# 04_FEATHER-CONNECTION.net
KiCad netlist of a schematic drawn in Altium Designer
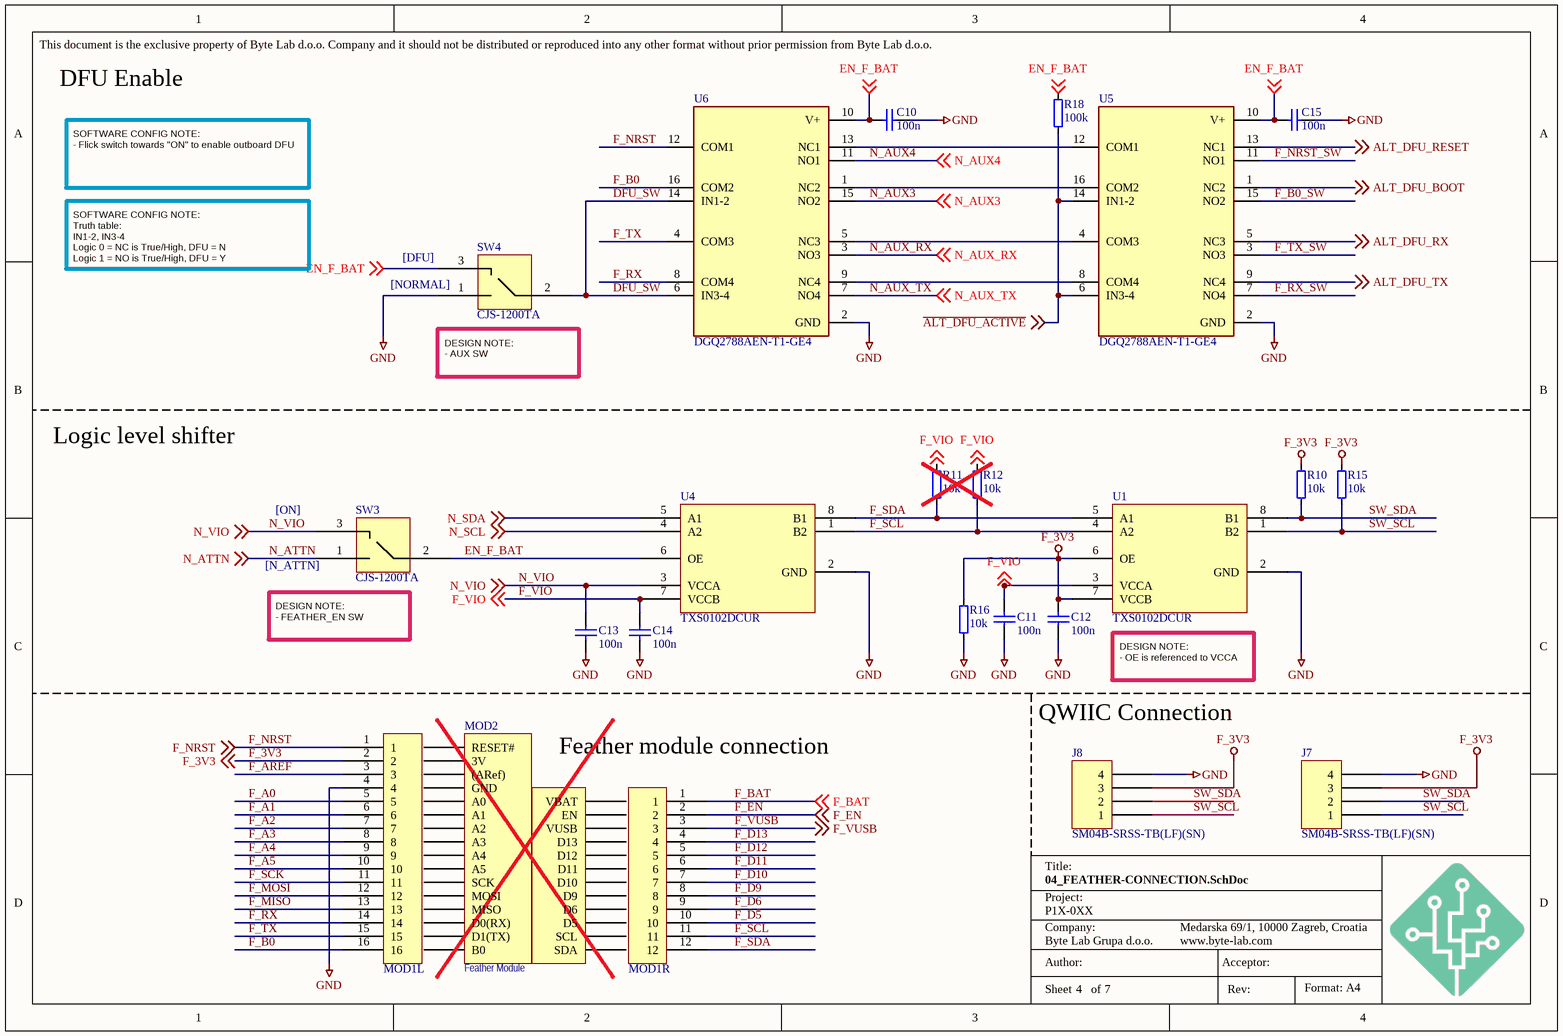
[diagram p0: 04_FEATHER-CONNECTION.SchDoc]

(export (version "E")
  (design (tool "Eeschema 10.0.6"))
  (components
    (comp (ref "C10")
      (value "100n")
      (footprint "C-0402")
      (description "Capacitor ceramic 100n ±10% X7R 16V 0402")
      (fields
        (field (name "BL PART NUMBER") "2000-908")
        (field (name "DRAWN_BY") "Puskar")
        (field (name "CHECKED_BY") "Dodig")
      )
      (libsource (lib "BL_Passive") (part "C0402-100n-16V-X7R"))
    )
    (comp (ref "C11")
      (value "100n")
      (footprint "C-0402")
      (description "Capacitor ceramic 100n ±10% X7R 16V 0402")
      (fields
        (field (name "BL PART NUMBER") "2000-908")
        (field (name "DRAWN_BY") "Puskar")
        (field (name "CHECKED_BY") "Dodig")
      )
      (libsource (lib "BL_Passive") (part "C0402-100n-16V-X7R"))
    )
    (comp (ref "C12")
      (value "100n")
      (footprint "C-0402")
      (description "Capacitor ceramic 100n ±10% X7R 16V 0402")
      (fields
        (field (name "BL PART NUMBER") "2000-908")
        (field (name "DRAWN_BY") "Puskar")
        (field (name "CHECKED_BY") "Dodig")
      )
      (libsource (lib "BL_Passive") (part "C0402-100n-16V-X7R"))
    )
    (comp (ref "C13")
      (value "100n")
      (footprint "C-0402")
      (description "Capacitor ceramic 100n ±10% X7R 16V 0402")
      (fields
        (field (name "BL PART NUMBER") "2000-908")
        (field (name "DRAWN_BY") "Puskar")
        (field (name "CHECKED_BY") "Dodig")
      )
      (libsource (lib "BL_Passive") (part "C0402-100n-16V-X7R"))
    )
    (comp (ref "C14")
      (value "100n")
      (footprint "C-0402")
      (description "Capacitor ceramic 100n ±10% X7R 16V 0402")
      (fields
        (field (name "BL PART NUMBER") "2000-908")
        (field (name "DRAWN_BY") "Puskar")
        (field (name "CHECKED_BY") "Dodig")
      )
      (libsource (lib "BL_Passive") (part "C0402-100n-16V-X7R"))
    )
    (comp (ref "C15")
      (value "100n")
      (footprint "C-0402")
      (description "Capacitor ceramic 100n ±10% X7R 16V 0402")
      (fields
        (field (name "BL PART NUMBER") "2000-908")
        (field (name "DRAWN_BY") "Puskar")
        (field (name "CHECKED_BY") "Dodig")
      )
      (libsource (lib "BL_Passive") (part "C0402-100n-16V-X7R"))
    )
    (comp (ref "J7")
      (value "SM04B-SRSS-TB(LF)(SN)")
      (footprint "JST SM04B-SRSS-TB")
      (description "CONN HEADER SH 4POS SIDE 1MM TIN")
      (fields
        (field (name "MANUFACTURER") "JST Sales America Inc.")
        (field (name "BL PART NUMBER") "2002-058")
        (field (name "DRAWN_BY") "Blues Wireless")
      )
      (libsource (lib "n21-p2") (part "SM04B-SRSS-TB(LF)(SN)"))
    )
    (comp (ref "J8")
      (value "SM04B-SRSS-TB(LF)(SN)")
      (footprint "JST SM04B-SRSS-TB")
      (description "CONN HEADER SH 4POS SIDE 1MM TIN")
      (fields
        (field (name "MANUFACTURER") "JST Sales America Inc.")
        (field (name "BL PART NUMBER") "2002-058")
        (field (name "DRAWN_BY") "Blues Wireless")
      )
      (libsource (lib "n21-p2") (part "SM04B-SRSS-TB(LF)(SN)"))
    )
    (comp (ref "MOD1L")
      (value "CES-116-01-L-S")
      (footprint "16PIN_254MM")
      (description "Socket 16-Pin, 0.100 in")
      (fields
        (field (name "MANUFACTURER") "Samtec Inc.")
        (field (name "BL PART NUMBER") "2007-463")
        (field (name "DRAWN_BY") "Blues Wireless")
      )
      (libsource (lib "n21-p2") (part "SOCKET_LFB_16"))
    )
    (comp (ref "MOD1R")
      (value "CES-112-01-L-S")
      (footprint "12PIN_254MM")
      (description "Socket 12-Pin, 0.100 in")
      (fields
        (field (name "MANUFACTURER") "Samtec Inc.")
        (field (name "BL PART NUMBER") "2007-464")
        (field (name "DRAWN_BY") "Blues Wireless")
      )
      (libsource (lib "n21-p2") (part "SOCKET_LFB_12"))
    )
    (comp (ref "MOD2")
      (value "Feather Module")
      (footprint "BLUES_WIRELESS_SWAN_2-54_HEADERS")
      (description "Typical Adafruit Feather Pinout")
      (libsource (lib "n21-p2") (part "ADAFRUIT_FEATHER_COMMON_1"))
    )
    (comp (ref "R10")
      (value "10k")
      (footprint "R-0402")
      (description "Resistor 10k ±1% 0402")
      (fields
        (field (name "BL PART NUMBER") "2000-729")
        (field (name "CHECKED_BY") "Dodig")
        (field (name "DRAWN_BY") "Puskar")
      )
      (libsource (lib "BL_Passive") (part "R0402-10k-1"))
    )
    (comp (ref "R11")
      (value "10k")
      (footprint "R-0402")
      (description "Resistor 10k ±1% 0402")
      (fields
        (field (name "BL PART NUMBER") "2000-729")
        (field (name "CHECKED_BY") "Dodig")
        (field (name "DRAWN_BY") "Puskar")
      )
      (libsource (lib "BL_Passive") (part "R0402-10k-1"))
    )
    (comp (ref "R12")
      (value "10k")
      (footprint "R-0402")
      (description "Resistor 10k ±1% 0402")
      (fields
        (field (name "BL PART NUMBER") "2000-729")
        (field (name "CHECKED_BY") "Dodig")
        (field (name "DRAWN_BY") "Puskar")
      )
      (libsource (lib "BL_Passive") (part "R0402-10k-1"))
    )
    (comp (ref "R15")
      (value "10k")
      (footprint "R-0402")
      (description "Resistor 10k ±1% 0402")
      (fields
        (field (name "BL PART NUMBER") "2000-729")
        (field (name "CHECKED_BY") "Dodig")
        (field (name "DRAWN_BY") "Puskar")
      )
      (libsource (lib "BL_Passive") (part "R0402-10k-1"))
    )
    (comp (ref "R16")
      (value "10k")
      (footprint "R-0402")
      (description "Resistor 10k ±1% 0402")
      (fields
        (field (name "BL PART NUMBER") "2000-729")
        (field (name "CHECKED_BY") "Dodig")
        (field (name "DRAWN_BY") "Puskar")
      )
      (libsource (lib "BL_Passive") (part "R0402-10k-1"))
    )
    (comp (ref "R18")
      (value "100k")
      (footprint "R-0402")
      (description "Resistor 100k ±1% 0402")
      (fields
        (field (name "BL PART NUMBER") "2000-727")
        (field (name "CHECKED_BY") "Dodig")
        (field (name "DRAWN_BY") "Puskar")
      )
      (libsource (lib "BL_Passive") (part "R0402-100k-1"))
    )
    (comp (ref "SW3")
      (value "CJS-1200TA")
      (footprint "SW_CJS-1200TA")
      (description "Switch Slide N.O./N.C. SPDT Raised Slide 0.1A 24VDC J-Hook SMD Embossed T/R")
      (fields
        (field (name "MANUFACTURER") "Nidec Copal")
        (field (name "BL PART NUMBER") "2007-456")
        (field (name "DRAWN_BY") "Blues Wireless")
      )
      (libsource (lib "n21-p2") (part "CJS-1200TA"))
    )
    (comp (ref "SW4")
      (value "CJS-1200TA")
      (footprint "SW_CJS-1200TA")
      (description "Switch Slide N.O./N.C. SPDT Raised Slide 0.1A 24VDC J-Hook SMD Embossed T/R")
      (fields
        (field (name "MANUFACTURER") "Nidec Copal")
        (field (name "BL PART NUMBER") "2007-456")
        (field (name "DRAWN_BY") "Blues Wireless")
      )
      (libsource (lib "n21-p2") (part "CJS-1200TA"))
    )
    (comp (ref "U1")
      (value "TXS0102DCUR")
      (footprint "SOP50P310X90-8N")
      (fields
        (field (name "MANUFACTURER") "Texas Instruments")
        (field (name "BL PART NUMBER") "2007-455")
        (field (name "DRAWN_BY") "Blues Wireless")
      )
      (libsource (lib "n21-p2") (part "TXS0102DCUR"))
    )
    (comp (ref "U4")
      (value "TXS0102DCUR")
      (footprint "SOP50P310X90-8N")
      (fields
        (field (name "MANUFACTURER") "Texas Instruments")
        (field (name "BL PART NUMBER") "2007-455")
        (field (name "DRAWN_BY") "Blues Wireless")
      )
      (libsource (lib "n21-p2") (part "TXS0102DCUR"))
    )
    (comp (ref "U5")
      (value "DGQ2788AEN-T1-GE4")
      (footprint "QFN40P260X180X60-16N")
      (description "Analog Switch Quad SPDT Automotive 16-Pin Mini-QFN T/R")
      (fields
        (field (name "MANUFACTURER") "Vishay")
        (field (name "BL PART NUMBER") "2007-457")
        (field (name "DRAWN_BY") "Blues Wireless")
      )
      (libsource (lib "n21-p2") (part "DGQ2788AEN-T1-GE4"))
    )
    (comp (ref "U6")
      (value "DGQ2788AEN-T1-GE4")
      (footprint "QFN40P260X180X60-16N")
      (description "Analog Switch Quad SPDT Automotive 16-Pin Mini-QFN T/R")
      (fields
        (field (name "MANUFACTURER") "Vishay")
        (field (name "BL PART NUMBER") "2007-457")
        (field (name "DRAWN_BY") "Blues Wireless")
      )
      (libsource (lib "n21-p2") (part "DGQ2788AEN-T1-GE4"))
    )
  )
  (nets
    (net (code "1") (name "/DFU_SW") (class "Default")
      (node (ref "SW4") (pin "2") (pinfunction "2_2") (pintype "passive"))
      (node (ref "U6") (pin "14") (pinfunction "IN1-2_14") (pintype "passive"))
      (node (ref "U6") (pin "6") (pinfunction "IN3-4_6") (pintype "passive"))
    )
    (net (code "2") (name "/F_A0") (class "Default")
      (node (ref "MOD1L") (pin "5") (pinfunction "5_5") (pintype "passive"))
    )
    (net (code "3") (name "/F_A1") (class "Default")
      (node (ref "MOD1L") (pin "6") (pinfunction "6_6") (pintype "passive"))
    )
    (net (code "4") (name "/F_A2") (class "Default")
      (node (ref "MOD1L") (pin "7") (pinfunction "7_7") (pintype "passive"))
    )
    (net (code "5") (name "/F_A3") (class "Default")
      (node (ref "MOD1L") (pin "8") (pinfunction "8_8") (pintype "passive"))
    )
    (net (code "6") (name "/F_A4") (class "Default")
      (node (ref "MOD1L") (pin "9") (pinfunction "9_9") (pintype "passive"))
    )
    (net (code "7") (name "/F_A5") (class "Default")
      (node (ref "MOD1L") (pin "10") (pinfunction "10_10") (pintype "passive"))
    )
    (net (code "8") (name "/F_AREF") (class "Default")
      (node (ref "MOD1L") (pin "3") (pinfunction "3_3") (pintype "passive"))
    )
    (net (code "9") (name "/F_B0") (class "Default")
      (node (ref "MOD1L") (pin "16") (pinfunction "16_16") (pintype "passive"))
      (node (ref "U6") (pin "16") (pinfunction "COM2_16") (pintype "passive"))
    )
    (net (code "10") (name "/F_B0_SW") (class "Default")
      (node (ref "U5") (pin "15") (pinfunction "NO2_15") (pintype "passive"))
    )
    (net (code "11") (name "/F_D5") (class "Default")
      (node (ref "MOD1R") (pin "10") (pinfunction "10_10") (pintype "passive"))
    )
    (net (code "12") (name "/F_D6") (class "Default")
      (node (ref "MOD1R") (pin "9") (pinfunction "9_9") (pintype "passive"))
    )
    (net (code "13") (name "/F_D9") (class "Default")
      (node (ref "MOD1R") (pin "8") (pinfunction "8_8") (pintype "passive"))
    )
    (net (code "14") (name "/F_D10") (class "Default")
      (node (ref "MOD1R") (pin "7") (pinfunction "7_7") (pintype "passive"))
    )
    (net (code "15") (name "/F_D11") (class "Default")
      (node (ref "MOD1R") (pin "6") (pinfunction "6_6") (pintype "passive"))
    )
    (net (code "16") (name "/F_D12") (class "Default")
      (node (ref "MOD1R") (pin "5") (pinfunction "5_5") (pintype "passive"))
    )
    (net (code "17") (name "/F_D13") (class "Default")
      (node (ref "MOD1R") (pin "4") (pinfunction "4_4") (pintype "passive"))
    )
    (net (code "18") (name "/F_MISO") (class "Default")
      (node (ref "MOD1L") (pin "13") (pinfunction "13_13") (pintype "passive"))
    )
    (net (code "19") (name "/F_MOSI") (class "Default")
      (node (ref "MOD1L") (pin "12") (pinfunction "12_12") (pintype "passive"))
    )
    (net (code "20") (name "/F_NRST_SW") (class "Default")
      (node (ref "U5") (pin "11") (pinfunction "NO1_11") (pintype "passive"))
    )
    (net (code "21") (name "/F_RX") (class "Default")
      (node (ref "MOD1L") (pin "14") (pinfunction "14_14") (pintype "passive"))
      (node (ref "U6") (pin "8") (pinfunction "COM4_8") (pintype "passive"))
    )
    (net (code "22") (name "/F_RX_SW") (class "Default")
      (node (ref "U5") (pin "7") (pinfunction "NO4_7") (pintype "passive"))
    )
    (net (code "23") (name "/F_SCK") (class "Default")
      (node (ref "MOD1L") (pin "11") (pinfunction "11_11") (pintype "passive"))
    )
    (net (code "24") (name "/F_SCL") (class "Default")
      (node (ref "MOD1R") (pin "11") (pinfunction "11_11") (pintype "passive"))
      (node (ref "R12") (pin "1") (pintype "passive"))
      (node (ref "U1") (pin "4") (pinfunction "A2_4") (pintype "passive"))
      (node (ref "U4") (pin "1") (pinfunction "B2_1") (pintype "passive"))
    )
    (net (code "25") (name "/F_SDA") (class "Default")
      (node (ref "MOD1R") (pin "12") (pinfunction "12_12") (pintype "passive"))
      (node (ref "R11") (pin "1") (pintype "passive"))
      (node (ref "U1") (pin "5") (pinfunction "A1_5") (pintype "passive"))
      (node (ref "U4") (pin "8") (pinfunction "B1_8") (pintype "passive"))
    )
    (net (code "26") (name "/F_TX") (class "Default")
      (node (ref "MOD1L") (pin "15") (pinfunction "15_15") (pintype "passive"))
      (node (ref "U6") (pin "4") (pinfunction "COM3_4") (pintype "passive"))
    )
    (net (code "27") (name "/F_TX_SW") (class "Default")
      (node (ref "U5") (pin "3") (pinfunction "NO3_3") (pintype "passive"))
    )
    (net (code "28") (name "/SW_SCL") (class "Default")
      (node (ref "J7") (pin "1") (pinfunction "1_1") (pintype "passive"))
      (node (ref "J8") (pin "1") (pinfunction "1_1") (pintype "passive"))
      (node (ref "R15") (pin "1") (pintype "passive"))
      (node (ref "U1") (pin "1") (pinfunction "B2_1") (pintype "passive"))
    )
    (net (code "29") (name "/SW_SDA") (class "Default")
      (node (ref "J7") (pin "2") (pinfunction "2_2") (pintype "passive"))
      (node (ref "J8") (pin "2") (pinfunction "2_2") (pintype "passive"))
      (node (ref "R10") (pin "1") (pintype "passive"))
      (node (ref "U1") (pin "8") (pinfunction "B1_8") (pintype "passive"))
    )
    (net (code "30") (name "ALT_DFU_ACTIVE") (class "Default")
      (node (ref "R18") (pin "1") (pintype "passive"))
      (node (ref "U5") (pin "14") (pinfunction "IN1-2_14") (pintype "passive"))
      (node (ref "U5") (pin "6") (pinfunction "IN3-4_6") (pintype "passive"))
    )
    (net (code "31") (name "ALT_DFU_BOOT") (class "Default")
      (node (ref "U5") (pin "1") (pinfunction "NC2_1") (pintype "passive"))
    )
    (net (code "32") (name "ALT_DFU_RESET") (class "Default")
      (node (ref "U5") (pin "13") (pinfunction "NC1_13") (pintype "passive"))
    )
    (net (code "33") (name "ALT_DFU_RX") (class "Default")
      (node (ref "U5") (pin "5") (pinfunction "NC3_5") (pintype "passive"))
    )
    (net (code "34") (name "ALT_DFU_TX") (class "Default")
      (node (ref "U5") (pin "9") (pinfunction "NC4_9") (pintype "passive"))
    )
    (net (code "35") (name "EN_F_BAT") (class "Default")
      (node (ref "C10") (pin "2") (pinfunction "2_2") (pintype "passive"))
      (node (ref "C15") (pin "2") (pinfunction "2_2") (pintype "passive"))
      (node (ref "R18") (pin "2") (pintype "passive"))
      (node (ref "SW3") (pin "2") (pinfunction "2_2") (pintype "passive"))
      (node (ref "SW4") (pin "3") (pinfunction "3_3") (pintype "passive"))
      (node (ref "U4") (pin "6") (pinfunction "OE_6") (pintype "passive"))
      (node (ref "U5") (pin "10") (pinfunction "V+_10") (pintype "power_in"))
      (node (ref "U6") (pin "10") (pinfunction "V+_10") (pintype "power_in"))
    )
    (net (code "36") (name "F_3V3") (class "Default")
      (node (ref "C12") (pin "1") (pinfunction "1_1") (pintype "passive"))
      (node (ref "J7") (pin "3") (pinfunction "3_3") (pintype "passive"))
      (node (ref "J8") (pin "3") (pinfunction "3_3") (pintype "passive"))
      (node (ref "MOD1L") (pin "2") (pinfunction "2_2") (pintype "passive"))
      (node (ref "R10") (pin "2") (pintype "passive"))
      (node (ref "R15") (pin "2") (pintype "passive"))
      (node (ref "R16") (pin "1") (pintype "passive"))
      (node (ref "U1") (pin "6") (pinfunction "OE_6") (pintype "passive"))
      (node (ref "U1") (pin "7") (pinfunction "VCCB_7") (pintype "passive"))
    )
    (net (code "37") (name "F_BAT") (class "Default")
      (node (ref "MOD1R") (pin "1") (pinfunction "1_1") (pintype "passive"))
    )
    (net (code "38") (name "F_EN") (class "Default")
      (node (ref "MOD1R") (pin "2") (pinfunction "2_2") (pintype "passive"))
    )
    (net (code "39") (name "F_NRST") (class "Default")
      (node (ref "MOD1L") (pin "1") (pinfunction "1_1") (pintype "passive"))
      (node (ref "U6") (pin "12") (pinfunction "COM1_12") (pintype "passive"))
    )
    (net (code "40") (name "F_VIO") (class "Default")
      (node (ref "C11") (pin "1") (pinfunction "1_1") (pintype "passive"))
      (node (ref "C14") (pin "1") (pinfunction "1_1") (pintype "passive"))
      (node (ref "R11") (pin "2") (pintype "passive"))
      (node (ref "R12") (pin "2") (pintype "passive"))
      (node (ref "U1") (pin "3") (pinfunction "VCCA_3") (pintype "passive"))
      (node (ref "U4") (pin "7") (pinfunction "VCCB_7") (pintype "passive"))
    )
    (net (code "41") (name "F_VUSB") (class "Default")
      (node (ref "MOD1R") (pin "3") (pinfunction "3_3") (pintype "passive"))
    )
    (net (code "42") (name "GND") (class "Default")
      (node (ref "C10") (pin "1") (pinfunction "1_1") (pintype "passive"))
      (node (ref "C11") (pin "2") (pinfunction "2_2") (pintype "passive"))
      (node (ref "C12") (pin "2") (pinfunction "2_2") (pintype "passive"))
      (node (ref "C13") (pin "2") (pinfunction "2_2") (pintype "passive"))
      (node (ref "C14") (pin "2") (pinfunction "2_2") (pintype "passive"))
      (node (ref "C15") (pin "1") (pinfunction "1_1") (pintype "passive"))
      (node (ref "J7") (pin "4") (pinfunction "4_4") (pintype "passive"))
      (node (ref "J8") (pin "4") (pinfunction "4_4") (pintype "passive"))
      (node (ref "MOD1L") (pin "4") (pinfunction "4_4") (pintype "passive"))
      (node (ref "R16") (pin "2") (pintype "passive"))
      (node (ref "SW4") (pin "1") (pinfunction "1_1") (pintype "passive"))
      (node (ref "U1") (pin "2") (pinfunction "GND_2") (pintype "passive"))
      (node (ref "U4") (pin "2") (pinfunction "GND_2") (pintype "passive"))
      (node (ref "U5") (pin "2") (pinfunction "GND_2") (pintype "power_in"))
      (node (ref "U6") (pin "2") (pinfunction "GND_2") (pintype "power_in"))
    )
    (net (code "43") (name "N_ATTN") (class "Default")
      (node (ref "SW3") (pin "1") (pinfunction "1_1") (pintype "passive"))
    )
    (net (code "44") (name "N_AUX3") (class "Default")
      (node (ref "U6") (pin "15") (pinfunction "NO2_15") (pintype "passive"))
    )
    (net (code "45") (name "N_AUX4") (class "Default")
      (node (ref "U6") (pin "11") (pinfunction "NO1_11") (pintype "passive"))
    )
    (net (code "46") (name "N_AUX_RX") (class "Default")
      (node (ref "U6") (pin "3") (pinfunction "NO3_3") (pintype "passive"))
    )
    (net (code "47") (name "N_AUX_TX") (class "Default")
      (node (ref "U6") (pin "7") (pinfunction "NO4_7") (pintype "passive"))
    )
    (net (code "48") (name "N_SCL") (class "Default")
      (node (ref "U4") (pin "4") (pinfunction "A2_4") (pintype "passive"))
    )
    (net (code "49") (name "N_SDA") (class "Default")
      (node (ref "U4") (pin "5") (pinfunction "A1_5") (pintype "passive"))
    )
    (net (code "50") (name "N_VIO") (class "Default")
      (node (ref "C13") (pin "1") (pinfunction "1_1") (pintype "passive"))
      (node (ref "SW3") (pin "3") (pinfunction "3_3") (pintype "passive"))
      (node (ref "U4") (pin "3") (pinfunction "VCCA_3") (pintype "passive"))
    )
    (net (code "51") (name "Net-(U5-COM1)") (class "Default")
      (node (ref "U5") (pin "12") (pinfunction "COM1_12") (pintype "passive"))
      (node (ref "U6") (pin "13") (pinfunction "NC1_13") (pintype "passive"))
    )
    (net (code "52") (name "Net-(U5-COM2)") (class "Default")
      (node (ref "U5") (pin "16") (pinfunction "COM2_16") (pintype "passive"))
      (node (ref "U6") (pin "1") (pinfunction "NC2_1") (pintype "passive"))
    )
    (net (code "53") (name "Net-(U5-COM3)") (class "Default")
      (node (ref "U5") (pin "4") (pinfunction "COM3_4") (pintype "passive"))
      (node (ref "U6") (pin "5") (pinfunction "NC3_5") (pintype "passive"))
    )
    (net (code "54") (name "Net-(U5-COM4)") (class "Default")
      (node (ref "U5") (pin "8") (pinfunction "COM4_8") (pintype "passive"))
      (node (ref "U6") (pin "9") (pinfunction "NC4_9") (pintype "passive"))
    )
    (net (code "55") (name "unconnected-(MOD2-(ARef)-Pad3)") (class "Default")
      (node (ref "MOD2") (pin "3") (pinfunction "(ARef)_3") (pintype "passive"))
    )
    (net (code "56") (name "unconnected-(MOD2-3V-Pad2)") (class "Default")
      (node (ref "MOD2") (pin "2") (pinfunction "3V_2") (pintype "passive"))
    )
    (net (code "57") (name "unconnected-(MOD2-A0-Pad5)") (class "Default")
      (node (ref "MOD2") (pin "5") (pinfunction "A0_5") (pintype "passive"))
    )
    (net (code "58") (name "unconnected-(MOD2-A1-Pad6)") (class "Default")
      (node (ref "MOD2") (pin "6") (pinfunction "A1_6") (pintype "passive"))
    )
    (net (code "59") (name "unconnected-(MOD2-A2-Pad7)") (class "Default")
      (node (ref "MOD2") (pin "7") (pinfunction "A2_7") (pintype "passive"))
    )
    (net (code "60") (name "unconnected-(MOD2-A3-Pad8)") (class "Default")
      (node (ref "MOD2") (pin "8") (pinfunction "A3_8") (pintype "passive"))
    )
    (net (code "61") (name "unconnected-(MOD2-A4-Pad9)") (class "Default")
      (node (ref "MOD2") (pin "9") (pinfunction "A4_9") (pintype "passive"))
    )
    (net (code "62") (name "unconnected-(MOD2-A5-Pad10)") (class "Default")
      (node (ref "MOD2") (pin "10") (pinfunction "A5_10") (pintype "passive"))
    )
    (net (code "63") (name "unconnected-(MOD2-B0-Pad16)") (class "Default")
      (node (ref "MOD2") (pin "16") (pinfunction "B0_16") (pintype "passive"))
    )
    (net (code "64") (name "unconnected-(MOD2-D0(RX)-Pad14)") (class "Default")
      (node (ref "MOD2") (pin "14") (pinfunction "D0(RX)_14") (pintype "passive"))
    )
    (net (code "65") (name "unconnected-(MOD2-D1(TX)-Pad15)") (class "Default")
      (node (ref "MOD2") (pin "15") (pinfunction "D1(TX)_15") (pintype "passive"))
    )
    (net (code "66") (name "unconnected-(MOD2-D5-Pad19)") (class "Default")
      (node (ref "MOD2") (pin "19") (pinfunction "D5_19") (pintype "passive"))
    )
    (net (code "67") (name "unconnected-(MOD2-D6-Pad20)") (class "Default")
      (node (ref "MOD2") (pin "20") (pinfunction "D6_20") (pintype "passive"))
    )
    (net (code "68") (name "unconnected-(MOD2-D9-Pad21)") (class "Default")
      (node (ref "MOD2") (pin "21") (pinfunction "D9_21") (pintype "passive"))
    )
    (net (code "69") (name "unconnected-(MOD2-D10-Pad22)") (class "Default")
      (node (ref "MOD2") (pin "22") (pinfunction "D10_22") (pintype "passive"))
    )
    (net (code "70") (name "unconnected-(MOD2-D11-Pad23)") (class "Default")
      (node (ref "MOD2") (pin "23") (pinfunction "D11_23") (pintype "passive"))
    )
    (net (code "71") (name "unconnected-(MOD2-D12-Pad24)") (class "Default")
      (node (ref "MOD2") (pin "24") (pinfunction "D12_24") (pintype "passive"))
    )
    (net (code "72") (name "unconnected-(MOD2-D13-Pad25)") (class "Default")
      (node (ref "MOD2") (pin "25") (pinfunction "D13_25") (pintype "passive"))
    )
    (net (code "73") (name "unconnected-(MOD2-EN-Pad27)") (class "Default")
      (node (ref "MOD2") (pin "27") (pinfunction "EN_27") (pintype "passive"))
    )
    (net (code "74") (name "unconnected-(MOD2-GND-Pad4)") (class "Default")
      (node (ref "MOD2") (pin "4") (pinfunction "GND_4") (pintype "passive"))
    )
    (net (code "75") (name "unconnected-(MOD2-MISO-Pad13)") (class "Default")
      (node (ref "MOD2") (pin "13") (pinfunction "MISO_13") (pintype "passive"))
    )
    (net (code "76") (name "unconnected-(MOD2-MOSI-Pad12)") (class "Default")
      (node (ref "MOD2") (pin "12") (pinfunction "MOSI_12") (pintype "passive"))
    )
    (net (code "77") (name "unconnected-(MOD2-RESET#-Pad1)") (class "Default")
      (node (ref "MOD2") (pin "1") (pinfunction "RESET#_1") (pintype "passive"))
    )
    (net (code "78") (name "unconnected-(MOD2-SCK-Pad11)") (class "Default")
      (node (ref "MOD2") (pin "11") (pinfunction "SCK_11") (pintype "passive"))
    )
    (net (code "79") (name "unconnected-(MOD2-SCL-Pad18)") (class "Default")
      (node (ref "MOD2") (pin "18") (pinfunction "SCL_18") (pintype "passive"))
    )
    (net (code "80") (name "unconnected-(MOD2-SDA-Pad17)") (class "Default")
      (node (ref "MOD2") (pin "17") (pinfunction "SDA_17") (pintype "passive"))
    )
    (net (code "81") (name "unconnected-(MOD2-VBAT-Pad28)") (class "Default")
      (node (ref "MOD2") (pin "28") (pinfunction "VBAT_28") (pintype "passive"))
    )
    (net (code "82") (name "unconnected-(MOD2-VUSB-Pad26)") (class "Default")
      (node (ref "MOD2") (pin "26") (pinfunction "VUSB_26") (pintype "passive"))
    )
  )
)
